# mod_panel_voltage.net
KiCad netlist of a schematic drawn in EAGLE
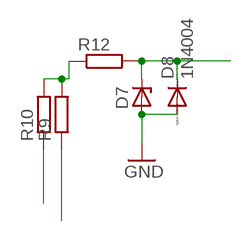
[diagram p0: schematic, sheet 1]

(export (version "E")
  (design (tool "Eeschema 10.0.6"))
  (components
    (comp (ref "D7")
      (value "ZENER-DIODEDO34-7")
      (footprint "eagle-import:DO34Z7")
      (libsource (lib "eagle-import") (part "ZENER-DIODEDO34-7"))
    )
    (comp (ref "D8")
      (value "1N4004")
      (footprint "eagle-import:DO41-10")
      (libsource (lib "eagle-import") (part "1N4004"))
    )
    (comp (ref "R9")
      (value "R-EU_0204/5")
      (footprint "eagle-import:0204_5")
      (libsource (lib "eagle-import") (part "R-EU_0204/5"))
    )
    (comp (ref "R10")
      (value "R-EU_0204/5")
      (footprint "eagle-import:0204_5")
      (libsource (lib "eagle-import") (part "R-EU_0204/5"))
    )
    (comp (ref "R12")
      (value "R-EU_0204/5")
      (footprint "eagle-import:0204_5")
      (libsource (lib "eagle-import") (part "R-EU_0204/5"))
    )
  )
  (nets
    (net (code "1") (name "GND") (class "Default")
      (node (ref "D7") (pin "A") (pinfunction "A_A") (pintype "passive"))
      (node (ref "D8") (pin "A") (pinfunction "A_A") (pintype "passive"))
    )
    (net (code "2") (name "Net-(D7-PadC)") (class "Default")
      (node (ref "D7") (pin "C") (pinfunction "C_C") (pintype "passive"))
      (node (ref "D8") (pin "C") (pinfunction "C_C") (pintype "passive"))
      (node (ref "R12") (pin "2") (pinfunction "2_2") (pintype "passive"))
    )
    (net (code "3") (name "Net-(R10-Pad2)") (class "Default")
      (node (ref "R10") (pin "2") (pinfunction "2_2") (pintype "passive"))
      (node (ref "R12") (pin "1") (pinfunction "1_1") (pintype "passive"))
      (node (ref "R9") (pin "2") (pinfunction "2_2") (pintype "passive"))
    )
    (net (code "4") (name "unconnected-(R9-Pad1)") (class "Default")
      (node (ref "R9") (pin "1") (pinfunction "1_1") (pintype "passive"))
    )
    (net (code "5") (name "unconnected-(R10-Pad1)") (class "Default")
      (node (ref "R10") (pin "1") (pinfunction "1_1") (pintype "passive"))
    )
  )
)
